# HX711_BrewSwitchSense_Preinfusion.net
KiCad netlist of a schematic drawn in EAGLE
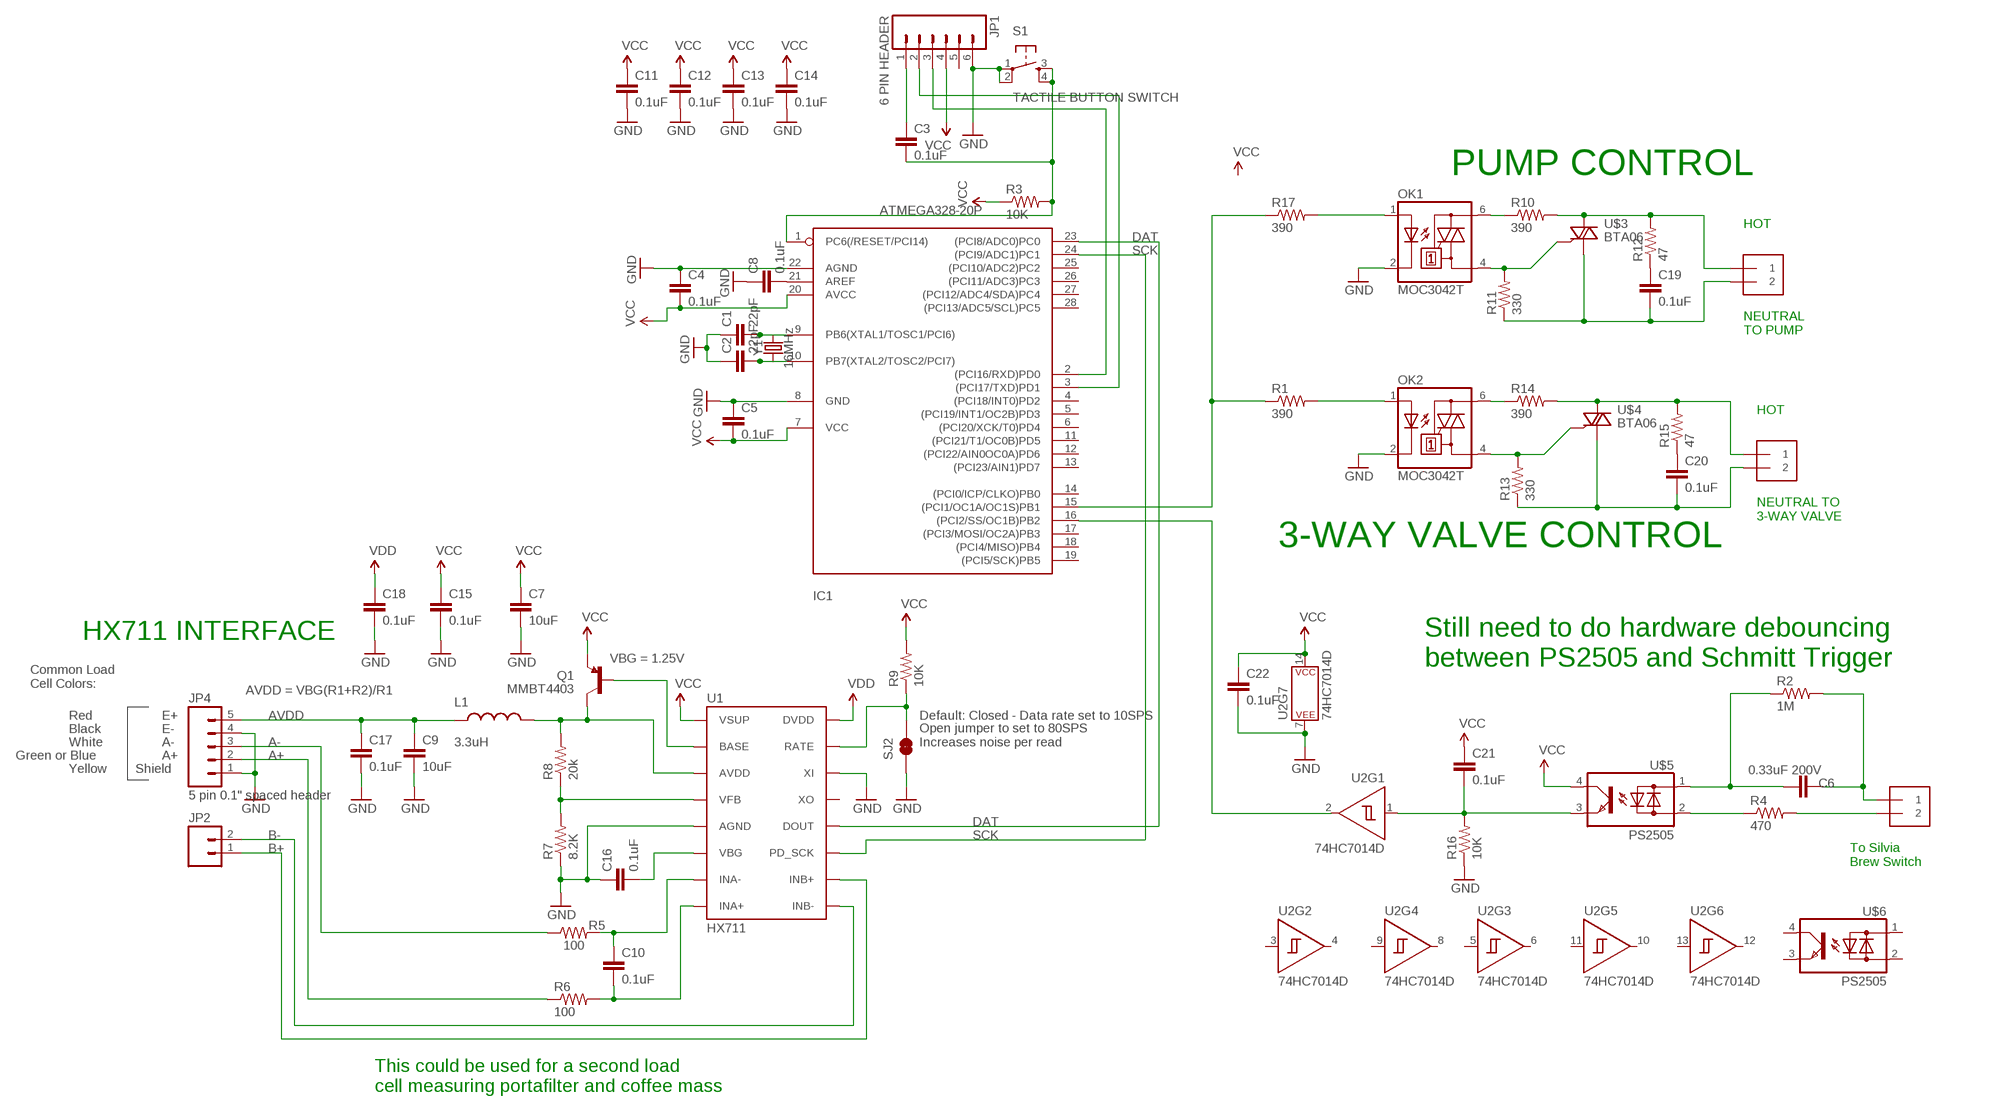
[diagram p0: schematic, sheet 1]

(export (version "E")
  (design (tool "Eeschema 10.0.6"))
  (components
    (comp (ref "C1")
      (value "22pF")
      (footprint "eagle-import:CAP-PTH-SMALL-KIT")
      (libsource (lib "eagle-import") (part "CAPKIT"))
    )
    (comp (ref "C2")
      (value "22pF")
      (footprint "eagle-import:CAP-PTH-SMALL-KIT")
      (libsource (lib "eagle-import") (part "CAPKIT"))
    )
    (comp (ref "C3")
      (value "0.1uF")
      (footprint "eagle-import:CAP-PTH-SMALLEZ")
      (libsource (lib "eagle-import") (part "CAPEZ"))
    )
    (comp (ref "C4")
      (value "0.1uF")
      (footprint "eagle-import:CAP-PTH-SMALLEZ")
      (libsource (lib "eagle-import") (part "CAPEZ"))
    )
    (comp (ref "C5")
      (value "0.1uF")
      (footprint "eagle-import:CAP-PTH-SMALLEZ")
      (libsource (lib "eagle-import") (part "CAPEZ"))
    )
    (comp (ref "C6")
      (value "0.33uF 200V")
      (footprint "eagle-import:C15B6")
      (libsource (lib "eagle-import") (part "C15/6"))
    )
    (comp (ref "C7")
      (value "10uF")
      (footprint "eagle-import:1210")
      (libsource (lib "eagle-import") (part "10UF50V20%(1210)"))
    )
    (comp (ref "C8")
      (value "0.1uF")
      (footprint "eagle-import:CAP-PTH-SMALLEZ")
      (libsource (lib "eagle-import") (part "CAPEZ"))
    )
    (comp (ref "C9")
      (value "10uF")
      (footprint "eagle-import:1210")
      (libsource (lib "eagle-import") (part "10UF50V20%(1210)"))
    )
    (comp (ref "C10")
      (value "0.1uF")
      (footprint "eagle-import:0603-CAP")
      (libsource (lib "eagle-import") (part "0.1UF-25V-5%(0603)"))
    )
    (comp (ref "C11")
      (value "0.1uF")
      (footprint "eagle-import:CAP-PTH-SMALLEZ")
      (libsource (lib "eagle-import") (part "CAPEZ"))
    )
    (comp (ref "C12")
      (value "0.1uF")
      (footprint "eagle-import:CAP-PTH-SMALLEZ")
      (libsource (lib "eagle-import") (part "CAPEZ"))
    )
    (comp (ref "C13")
      (value "0.1uF")
      (footprint "eagle-import:CAP-PTH-SMALLEZ")
      (libsource (lib "eagle-import") (part "CAPEZ"))
    )
    (comp (ref "C14")
      (value "0.1uF")
      (footprint "eagle-import:CAP-PTH-SMALLEZ")
      (libsource (lib "eagle-import") (part "CAPEZ"))
    )
    (comp (ref "C15")
      (value "0.1uF")
      (footprint "eagle-import:0603-CAP")
      (libsource (lib "eagle-import") (part "0.1UF-25V-5%(0603)"))
    )
    (comp (ref "C16")
      (value "0.1uF")
      (footprint "eagle-import:0603-CAP")
      (libsource (lib "eagle-import") (part "0.1UF-25V-5%(0603)"))
    )
    (comp (ref "C17")
      (value "0.1uF")
      (footprint "eagle-import:0603-CAP")
      (libsource (lib "eagle-import") (part "0.1UF-25V-5%(0603)"))
    )
    (comp (ref "C18")
      (value "0.1uF")
      (footprint "eagle-import:0603-CAP")
      (libsource (lib "eagle-import") (part "0.1UF-25V-5%(0603)"))
    )
    (comp (ref "C19")
      (value "0.1uF")
      (footprint "eagle-import:CAP-PTH-SMALLEZ")
      (libsource (lib "eagle-import") (part "CAPEZ"))
    )
    (comp (ref "C20")
      (value "0.1uF")
      (footprint "eagle-import:CAP-PTH-SMALLEZ")
      (libsource (lib "eagle-import") (part "CAPEZ"))
    )
    (comp (ref "C21")
      (value "0.1uF")
      (footprint "eagle-import:CAP-PTH-SMALLEZ")
      (libsource (lib "eagle-import") (part "CAPEZ"))
    )
    (comp (ref "C22")
      (value "0.1uF")
      (footprint "eagle-import:CAP-PTH-SMALLEZ")
      (libsource (lib "eagle-import") (part "CAPEZ"))
    )
    (comp (ref "IC1")
      (value "ATMEGA328-20P")
      (footprint "eagle-import:DIL28-3")
      (libsource (lib "eagle-import") (part "ATMEGA328P-20"))
    )
    (comp (ref "J2")
      (value "1X2-3.5MM")
      (footprint "eagle-import:1X2-3.5MM")
      (libsource (lib "eagle-import") (part "1X2-3.5MM"))
    )
    (comp (ref "J3")
      (value "1X2-3.5MM")
      (footprint "eagle-import:1X2-3.5MM")
      (libsource (lib "eagle-import") (part "1X2-3.5MM"))
    )
    (comp (ref "J4")
      (value "1X2-3.5MM")
      (footprint "eagle-import:1X2-3.5MM")
      (libsource (lib "eagle-import") (part "1X2-3.5MM"))
    )
    (comp (ref "JP1")
      (value "6 PIN HEADER")
      (footprint "eagle-import:1X06_LOCK_LONGPADS")
      (libsource (lib "eagle-import") (part "M06LOCK_LONGPADS"))
    )
    (comp (ref "JP2")
      (value "M02PTH")
      (footprint "eagle-import:1X02")
      (libsource (lib "eagle-import") (part "M02PTH"))
    )
    (comp (ref "JP4")
      (value "5 pin 0.1\" spaced header")
      (footprint "eagle-import:1X05")
      (libsource (lib "eagle-import") (part "M05PTH"))
    )
    (comp (ref "L1")
      (value "3.3uH")
      (footprint "eagle-import:0805")
      (libsource (lib "eagle-import") (part "INDUCTOR0805-IND"))
    )
    (comp (ref "OK1")
      (value "MOC3042T")
      (footprint "eagle-import:DIL06B")
      (libsource (lib "eagle-import") (part "MOC30T42"))
    )
    (comp (ref "OK2")
      (value "MOC3042T")
      (footprint "eagle-import:DIL06B")
      (libsource (lib "eagle-import") (part "MOC30T42"))
    )
    (comp (ref "Q1")
      (value "MMBT4403")
      (footprint "eagle-import:SOT23-3")
      (libsource (lib "eagle-import") (part "TRANSISTOR_PNPMMBT4403"))
    )
    (comp (ref "R1")
      (value "390")
      (footprint "eagle-import:AXIAL-0.5")
      (libsource (lib "eagle-import") (part "RESISTORPTH-1/2W"))
    )
    (comp (ref "R2")
      (value "1M")
      (footprint "eagle-import:1_6W-RES")
      (libsource (lib "eagle-import") (part "RESISTORPTH-1/6W"))
    )
    (comp (ref "R3")
      (value "10K")
      (footprint "eagle-import:AXIAL-0.5")
      (libsource (lib "eagle-import") (part "RESISTORPTH-1/2W"))
    )
    (comp (ref "R4")
      (value "470")
      (footprint "eagle-import:AXIAL-0.3-KIT")
      (libsource (lib "eagle-import") (part "RESISTORKIT"))
    )
    (comp (ref "R5")
      (value "100")
      (footprint "eagle-import:0603-RES")
      (libsource (lib "eagle-import") (part "100OHM-1/10W-1%(0603)"))
    )
    (comp (ref "R6")
      (value "100")
      (footprint "eagle-import:0603-RES")
      (libsource (lib "eagle-import") (part "100OHM-1/10W-1%(0603)"))
    )
    (comp (ref "R7")
      (value "8.2K")
      (footprint "eagle-import:0603-RES")
      (libsource (lib "eagle-import") (part "8.2KOHM-1/10W-5%(0603)"))
    )
    (comp (ref "R8")
      (value "20k")
      (footprint "eagle-import:0603-RES")
      (libsource (lib "eagle-import") (part "20KOHM1/10W1%(0603)"))
    )
    (comp (ref "R9")
      (value "10K")
      (footprint "eagle-import:0603-RES")
      (libsource (lib "eagle-import") (part "10KOHM-1/10W-1%(0603)0603"))
    )
    (comp (ref "R10")
      (value "390")
      (footprint "eagle-import:AXIAL-0.5")
      (libsource (lib "eagle-import") (part "RESISTORPTH-1/2W"))
    )
    (comp (ref "R11")
      (value "330")
      (footprint "eagle-import:AXIAL-0.5")
      (libsource (lib "eagle-import") (part "RESISTORPTH-1/2W"))
    )
    (comp (ref "R12")
      (value "47")
      (footprint "eagle-import:AXIAL-0.5")
      (libsource (lib "eagle-import") (part "RESISTORPTH-1/2W"))
    )
    (comp (ref "R13")
      (value "330")
      (footprint "eagle-import:AXIAL-0.5")
      (libsource (lib "eagle-import") (part "RESISTORPTH-1/2W"))
    )
    (comp (ref "R14")
      (value "390")
      (footprint "eagle-import:AXIAL-0.5")
      (libsource (lib "eagle-import") (part "RESISTORPTH-1/2W"))
    )
    (comp (ref "R15")
      (value "47")
      (footprint "eagle-import:AXIAL-0.5")
      (libsource (lib "eagle-import") (part "RESISTORPTH-1/2W"))
    )
    (comp (ref "R16")
      (value "10K")
      (footprint "eagle-import:AXIAL-0.5")
      (libsource (lib "eagle-import") (part "RESISTORPTH-1/2W"))
    )
    (comp (ref "R17")
      (value "390")
      (footprint "eagle-import:AXIAL-0.5")
      (libsource (lib "eagle-import") (part "RESISTORPTH-1/2W"))
    )
    (comp (ref "S1")
      (value "TACTILE BUTTON SWITCH")
      (footprint "eagle-import:TACTILE-PTH")
      (libsource (lib "eagle-import") (part "TAC_SWITCHPTH"))
    )
    (comp (ref "SJ2")
      (value "JUMPER-PAD-2-NC_BY_TRACE")
      (footprint "eagle-import:PAD-JUMPER-2-NC_BY_TRACE_YES_SILK")
      (libsource (lib "eagle-import") (part "JUMPER-PAD-2-NC_BY_TRACE"))
    )
    (comp (ref "U$3")
      (value "BTA06")
      (footprint "eagle-import:TO220V")
      (libsource (lib "eagle-import") (part "BTA06"))
    )
    (comp (ref "U$4")
      (value "BTA06")
      (footprint "eagle-import:TO220V")
      (libsource (lib "eagle-import") (part "BTA06"))
    )
    (comp (ref "U$5")
      (value "PS2505")
      (footprint "eagle-import:DIL04")
      (libsource (lib "eagle-import") (part "PS2505"))
    )
    (comp (ref "U$6")
      (value "PS2505")
      (footprint "eagle-import:DIL04")
      (libsource (lib "eagle-import") (part "PS2505"))
    )
    (comp (ref "U1")
      (value "HX711")
      (footprint "eagle-import:SO16")
      (libsource (lib "eagle-import") (part "HX711HX711"))
    )
    (comp (ref "U2")
      (value "74HC7014D")
      (footprint "eagle-import:SO14")
      (libsource (lib "eagle-import") (part "747014DHC"))
    )
    (comp (ref "Y1")
      (value "16MHz")
      (footprint "eagle-import:HC49US")
      (libsource (lib "eagle-import") (part "CRYSTAL-16MHZPTH-HC49US"))
    )
  )
  (nets
    (net (code "1") (name "/A+") (class "Default")
      (node (ref "JP4") (pin "2") (pinfunction "2_2") (pintype "passive"))
      (node (ref "R6") (pin "1") (pinfunction "1_1") (pintype "passive"))
    )
    (net (code "2") (name "/A-") (class "Default")
      (node (ref "JP4") (pin "3") (pinfunction "3_3") (pintype "passive"))
      (node (ref "R5") (pin "1") (pinfunction "1_1") (pintype "passive"))
    )
    (net (code "3") (name "/AVDD") (class "Default")
      (node (ref "C17") (pin "1") (pinfunction "1_1") (pintype "passive"))
      (node (ref "C9") (pin "1") (pinfunction "1_1") (pintype "passive"))
      (node (ref "JP4") (pin "5") (pinfunction "5_5") (pintype "passive"))
      (node (ref "L1") (pin "1") (pinfunction "1_1") (pintype "passive"))
    )
    (net (code "4") (name "/B+") (class "Default")
      (node (ref "JP2") (pin "1") (pinfunction "1_1") (pintype "passive"))
      (node (ref "U1") (pin "10") (pinfunction "INB+_10") (pintype "bidirectional"))
    )
    (net (code "5") (name "/B-") (class "Default")
      (node (ref "JP2") (pin "2") (pinfunction "2_2") (pintype "passive"))
      (node (ref "U1") (pin "9") (pinfunction "INB-_9") (pintype "bidirectional"))
    )
    (net (code "6") (name "/DAT") (class "Default")
      (node (ref "IC1") (pin "23") (pinfunction "(PCI8/ADC0)PC0_23") (pintype "bidirectional"))
      (node (ref "U1") (pin "12") (pinfunction "DOUT_12") (pintype "bidirectional"))
    )
    (net (code "7") (name "/SCK") (class "Default")
      (node (ref "IC1") (pin "24") (pinfunction "(PCI9/ADC1)PC1_24") (pintype "bidirectional"))
      (node (ref "U1") (pin "11") (pinfunction "PD_SCK_11") (pintype "bidirectional"))
    )
    (net (code "8") (name "GND") (class "Default")
      (node (ref "C1") (pin "1") (pinfunction "1_1") (pintype "passive"))
      (node (ref "C11") (pin "2") (pinfunction "2_2") (pintype "passive"))
      (node (ref "C12") (pin "2") (pinfunction "2_2") (pintype "passive"))
      (node (ref "C13") (pin "2") (pinfunction "2_2") (pintype "passive"))
      (node (ref "C14") (pin "2") (pinfunction "2_2") (pintype "passive"))
      (node (ref "C15") (pin "2") (pinfunction "2_2") (pintype "passive"))
      (node (ref "C16") (pin "1") (pinfunction "1_1") (pintype "passive"))
      (node (ref "C17") (pin "2") (pinfunction "2_2") (pintype "passive"))
      (node (ref "C18") (pin "2") (pinfunction "2_2") (pintype "passive"))
      (node (ref "C2") (pin "1") (pinfunction "1_1") (pintype "passive"))
      (node (ref "C22") (pin "2") (pinfunction "2_2") (pintype "passive"))
      (node (ref "C4") (pin "1") (pinfunction "1_1") (pintype "passive"))
      (node (ref "C5") (pin "1") (pinfunction "1_1") (pintype "passive"))
      (node (ref "C7") (pin "2") (pinfunction "2_2") (pintype "passive"))
      (node (ref "C8") (pin "1") (pinfunction "1_1") (pintype "passive"))
      (node (ref "C9") (pin "2") (pinfunction "2_2") (pintype "passive"))
      (node (ref "IC1") (pin "22") (pinfunction "AGND_22") (pintype "bidirectional"))
      (node (ref "IC1") (pin "8") (pinfunction "GND_8") (pintype "bidirectional"))
      (node (ref "JP1") (pin "6") (pinfunction "6_6") (pintype "passive"))
      (node (ref "JP4") (pin "1") (pinfunction "1_1") (pintype "passive"))
      (node (ref "JP4") (pin "4") (pinfunction "4_4") (pintype "passive"))
      (node (ref "OK1") (pin "2") (pinfunction "C_2") (pintype "passive"))
      (node (ref "OK2") (pin "2") (pinfunction "C_2") (pintype "passive"))
      (node (ref "R16") (pin "P$1") (pinfunction "1_P$1") (pintype "passive"))
      (node (ref "R7") (pin "1") (pinfunction "1_1") (pintype "passive"))
      (node (ref "S1") (pin "1") (pinfunction "1_1") (pintype "passive"))
      (node (ref "S1") (pin "2") (pinfunction "2_2") (pintype "passive"))
      (node (ref "SJ2") (pin "1") (pinfunction "1_1") (pintype "passive"))
      (node (ref "U1") (pin "14") (pinfunction "XI_14") (pintype "bidirectional"))
      (node (ref "U1") (pin "5") (pinfunction "AGND_5") (pintype "bidirectional"))
      (node (ref "U2") (pin "7") (pinfunction "P$V-_7") (pintype "bidirectional"))
    )
    (net (code "9") (name "Net-(C3-Pad1)") (class "Default")
      (node (ref "C3") (pin "1") (pinfunction "1_1") (pintype "passive"))
      (node (ref "JP1") (pin "1") (pinfunction "1_1") (pintype "passive"))
    )
    (net (code "10") (name "Net-(C6-Pad2)") (class "Default")
      (node (ref "C6") (pin "2") (pinfunction "2_2") (pintype "passive"))
      (node (ref "J2") (pin "1") (pinfunction "1_1") (pintype "passive"))
      (node (ref "R2") (pin "2") (pinfunction "2_2") (pintype "passive"))
    )
    (net (code "11") (name "Net-(IC1-(PCI1{slash}OC1A{slash}OC1S)PB1)") (class "Default")
      (node (ref "IC1") (pin "15") (pinfunction "(PCI1/OC1A/OC1S)PB1_15") (pintype "bidirectional"))
      (node (ref "R1") (pin "P$1") (pinfunction "1_P$1") (pintype "passive"))
      (node (ref "R17") (pin "P$1") (pinfunction "1_P$1") (pintype "passive"))
    )
    (net (code "12") (name "Net-(IC1-(PCI2{slash}SS{slash}OC1B)PB2)") (class "Default")
      (node (ref "IC1") (pin "16") (pinfunction "(PCI2/SS/OC1B)PB2_16") (pintype "bidirectional"))
      (node (ref "U2") (pin "2") (pinfunction "Y_2") (pintype "bidirectional"))
    )
    (net (code "13") (name "Net-(IC1-(PCI16{slash}RXD)PD0)") (class "Default")
      (node (ref "IC1") (pin "2") (pinfunction "(PCI16/RXD)PD0_2") (pintype "bidirectional"))
      (node (ref "JP1") (pin "3") (pinfunction "3_3") (pintype "passive"))
    )
    (net (code "14") (name "Net-(IC1-(PCI17{slash}TXD)PD1)") (class "Default")
      (node (ref "IC1") (pin "3") (pinfunction "(PCI17/TXD)PD1_3") (pintype "bidirectional"))
      (node (ref "JP1") (pin "2") (pinfunction "2_2") (pintype "passive"))
    )
    (net (code "15") (name "Net-(IC1-AREF)") (class "Default")
      (node (ref "C8") (pin "2") (pinfunction "2_2") (pintype "passive"))
      (node (ref "IC1") (pin "21") (pinfunction "AREF_21") (pintype "bidirectional"))
    )
    (net (code "16") (name "Net-(IC1-PB6(XTAL1{slash}TOSC1{slash}PCI6))") (class "Default")
      (node (ref "C1") (pin "2") (pinfunction "2_2") (pintype "passive"))
      (node (ref "IC1") (pin "9") (pinfunction "PB6(XTAL1/TOSC1/PCI6)_9") (pintype "bidirectional"))
      (node (ref "Y1") (pin "2") (pinfunction "2_2") (pintype "passive"))
    )
    (net (code "17") (name "Net-(IC1-PB7(XTAL2{slash}TOSC2{slash}PCI7))") (class "Default")
      (node (ref "C2") (pin "2") (pinfunction "2_2") (pintype "passive"))
      (node (ref "IC1") (pin "10") (pinfunction "PB7(XTAL2/TOSC2/PCI7)_10") (pintype "bidirectional"))
      (node (ref "Y1") (pin "1") (pinfunction "1_1") (pintype "passive"))
    )
    (net (code "18") (name "Net-(IC1-PC6({slash}RESET{slash}PCI14))") (class "Default")
      (node (ref "C3") (pin "2") (pinfunction "2_2") (pintype "passive"))
      (node (ref "IC1") (pin "1") (pinfunction "PC6(/RESET/PCI14)_1") (pintype "bidirectional"))
      (node (ref "R3") (pin "P$2") (pinfunction "2_P$2") (pintype "passive"))
      (node (ref "S1") (pin "3") (pinfunction "3_3") (pintype "passive"))
      (node (ref "S1") (pin "4") (pinfunction "4_4") (pintype "passive"))
    )
    (net (code "19") (name "Net-(OK1-A)") (class "Default")
      (node (ref "OK1") (pin "1") (pinfunction "A_1") (pintype "passive"))
      (node (ref "R17") (pin "P$2") (pinfunction "2_P$2") (pintype "passive"))
    )
    (net (code "20") (name "Net-(OK1-A1)") (class "Default")
      (node (ref "OK1") (pin "4") (pinfunction "A1_4") (pintype "passive"))
      (node (ref "R11") (pin "P$2") (pinfunction "2_P$2") (pintype "passive"))
      (node (ref "U$3") (pin "3") (pinfunction "G_3") (pintype "passive"))
    )
    (net (code "21") (name "Net-(OK1-A2)") (class "Default")
      (node (ref "OK1") (pin "6") (pinfunction "A2_6") (pintype "passive"))
      (node (ref "R10") (pin "P$1") (pinfunction "1_P$1") (pintype "passive"))
    )
    (net (code "22") (name "Net-(OK2-A)") (class "Default")
      (node (ref "OK2") (pin "1") (pinfunction "A_1") (pintype "passive"))
      (node (ref "R1") (pin "P$2") (pinfunction "2_P$2") (pintype "passive"))
    )
    (net (code "23") (name "Net-(OK2-A1)") (class "Default")
      (node (ref "OK2") (pin "4") (pinfunction "A1_4") (pintype "passive"))
      (node (ref "R13") (pin "P$2") (pinfunction "2_P$2") (pintype "passive"))
      (node (ref "U$4") (pin "3") (pinfunction "G_3") (pintype "passive"))
    )
    (net (code "24") (name "Net-(OK2-A2)") (class "Default")
      (node (ref "OK2") (pin "6") (pinfunction "A2_6") (pintype "passive"))
      (node (ref "R14") (pin "P$1") (pinfunction "1_P$1") (pintype "passive"))
    )
    (net (code "25") (name "Net-(Q1-B)") (class "Default")
      (node (ref "Q1") (pin "1") (pinfunction "B_1") (pintype "passive"))
      (node (ref "U1") (pin "2") (pinfunction "BASE_2") (pintype "bidirectional"))
    )
    (net (code "26") (name "Net-(Q1-C)") (class "Default")
      (node (ref "L1") (pin "2") (pinfunction "2_2") (pintype "passive"))
      (node (ref "Q1") (pin "3") (pinfunction "C_3") (pintype "passive"))
      (node (ref "R8") (pin "2") (pinfunction "2_2") (pintype "passive"))
      (node (ref "U1") (pin "3") (pinfunction "AVDD_3") (pintype "bidirectional"))
    )
    (net (code "27") (name "Net-(R4-1)") (class "Default")
      (node (ref "R4") (pin "P$1") (pinfunction "1_P$1") (pintype "passive"))
      (node (ref "U$5") (pin "2") (pinfunction "AC2_2") (pintype "passive"))
    )
    (net (code "28") (name "Net-(R4-2)") (class "Default")
      (node (ref "J2") (pin "2") (pinfunction "2_2") (pintype "passive"))
      (node (ref "R4") (pin "P$2") (pinfunction "2_P$2") (pintype "passive"))
    )
    (net (code "29") (name "Net-(R10-2)") (class "Default")
      (node (ref "J3") (pin "1") (pinfunction "1_1") (pintype "passive"))
      (node (ref "R10") (pin "P$2") (pinfunction "2_P$2") (pintype "passive"))
      (node (ref "R12") (pin "P$2") (pinfunction "2_P$2") (pintype "passive"))
      (node (ref "U$3") (pin "2") (pinfunction "A2_2") (pintype "passive"))
    )
    (net (code "30") (name "Net-(R11-1)") (class "Default")
      (node (ref "C19") (pin "2") (pinfunction "2_2") (pintype "passive"))
      (node (ref "J3") (pin "2") (pinfunction "2_2") (pintype "passive"))
      (node (ref "R11") (pin "P$1") (pinfunction "1_P$1") (pintype "passive"))
      (node (ref "U$3") (pin "1") (pinfunction "A1_1") (pintype "passive"))
    )
    (net (code "31") (name "Net-(R12-1)") (class "Default")
      (node (ref "C19") (pin "1") (pinfunction "1_1") (pintype "passive"))
      (node (ref "R12") (pin "P$1") (pinfunction "1_P$1") (pintype "passive"))
    )
    (net (code "32") (name "Net-(R13-1)") (class "Default")
      (node (ref "C20") (pin "2") (pinfunction "2_2") (pintype "passive"))
      (node (ref "J4") (pin "2") (pinfunction "2_2") (pintype "passive"))
      (node (ref "R13") (pin "P$1") (pinfunction "1_P$1") (pintype "passive"))
      (node (ref "U$4") (pin "1") (pinfunction "A1_1") (pintype "passive"))
    )
    (net (code "33") (name "Net-(R14-2)") (class "Default")
      (node (ref "J4") (pin "1") (pinfunction "1_1") (pintype "passive"))
      (node (ref "R14") (pin "P$2") (pinfunction "2_P$2") (pintype "passive"))
      (node (ref "R15") (pin "P$2") (pinfunction "2_P$2") (pintype "passive"))
      (node (ref "U$4") (pin "2") (pinfunction "A2_2") (pintype "passive"))
    )
    (net (code "34") (name "Net-(R15-1)") (class "Default")
      (node (ref "C20") (pin "1") (pinfunction "1_1") (pintype "passive"))
      (node (ref "R15") (pin "P$1") (pinfunction "1_P$1") (pintype "passive"))
    )
    (net (code "35") (name "Net-(R16-2)") (class "Default")
      (node (ref "C21") (pin "2") (pinfunction "2_2") (pintype "passive"))
      (node (ref "R16") (pin "P$2") (pinfunction "2_P$2") (pintype "passive"))
      (node (ref "U$5") (pin "3") (pinfunction "E_3") (pintype "passive"))
      (node (ref "U2") (pin "1") (pinfunction "A_1") (pintype "bidirectional"))
    )
    (net (code "36") (name "Net-(U$5-AC1)") (class "Default")
      (node (ref "C6") (pin "1") (pinfunction "1_1") (pintype "passive"))
      (node (ref "R2") (pin "1") (pinfunction "1_1") (pintype "passive"))
      (node (ref "U$5") (pin "1") (pinfunction "AC1_1") (pintype "passive"))
    )
    (net (code "37") (name "Net-(U1-INA+)") (class "Default")
      (node (ref "C10") (pin "2") (pinfunction "2_2") (pintype "passive"))
      (node (ref "R6") (pin "2") (pinfunction "2_2") (pintype "passive"))
      (node (ref "U1") (pin "8") (pinfunction "INA+_8") (pintype "bidirectional"))
    )
    (net (code "38") (name "Net-(U1-INA-)") (class "Default")
      (node (ref "C10") (pin "1") (pinfunction "1_1") (pintype "passive"))
      (node (ref "R5") (pin "2") (pinfunction "2_2") (pintype "passive"))
      (node (ref "U1") (pin "7") (pinfunction "INA-_7") (pintype "bidirectional"))
    )
    (net (code "39") (name "Net-(U1-RATE)") (class "Default")
      (node (ref "R9") (pin "1") (pinfunction "1_1") (pintype "passive"))
      (node (ref "SJ2") (pin "2") (pinfunction "2_2") (pintype "passive"))
      (node (ref "U1") (pin "15") (pinfunction "RATE_15") (pintype "bidirectional"))
    )
    (net (code "40") (name "Net-(U1-VBG)") (class "Default")
      (node (ref "C16") (pin "2") (pinfunction "2_2") (pintype "passive"))
      (node (ref "U1") (pin "6") (pinfunction "VBG_6") (pintype "bidirectional"))
    )
    (net (code "41") (name "Net-(U1-VFB)") (class "Default")
      (node (ref "R7") (pin "2") (pinfunction "2_2") (pintype "passive"))
      (node (ref "R8") (pin "1") (pinfunction "1_1") (pintype "passive"))
      (node (ref "U1") (pin "4") (pinfunction "VFB_4") (pintype "bidirectional"))
    )
    (net (code "42") (name "VCC") (class "Default")
      (node (ref "C11") (pin "1") (pinfunction "1_1") (pintype "passive"))
      (node (ref "C12") (pin "1") (pinfunction "1_1") (pintype "passive"))
      (node (ref "C13") (pin "1") (pinfunction "1_1") (pintype "passive"))
      (node (ref "C14") (pin "1") (pinfunction "1_1") (pintype "passive"))
      (node (ref "C15") (pin "1") (pinfunction "1_1") (pintype "passive"))
      (node (ref "C21") (pin "1") (pinfunction "1_1") (pintype "passive"))
      (node (ref "C22") (pin "1") (pinfunction "1_1") (pintype "passive"))
      (node (ref "C4") (pin "2") (pinfunction "2_2") (pintype "passive"))
      (node (ref "C5") (pin "2") (pinfunction "2_2") (pintype "passive"))
      (node (ref "C7") (pin "1") (pinfunction "1_1") (pintype "passive"))
      (node (ref "IC1") (pin "20") (pinfunction "AVCC_20") (pintype "bidirectional"))
      (node (ref "IC1") (pin "7") (pinfunction "VCC_7") (pintype "bidirectional"))
      (node (ref "JP1") (pin "4") (pinfunction "4_4") (pintype "passive"))
      (node (ref "Q1") (pin "2") (pinfunction "E_2") (pintype "passive"))
      (node (ref "R3") (pin "P$1") (pinfunction "1_P$1") (pintype "passive"))
      (node (ref "R9") (pin "2") (pinfunction "2_2") (pintype "passive"))
      (node (ref "U$5") (pin "4") (pinfunction "C_4") (pintype "passive"))
      (node (ref "U1") (pin "1") (pinfunction "VSUP_1") (pintype "bidirectional"))
      (node (ref "U2") (pin "14") (pinfunction "P$V+_14") (pintype "bidirectional"))
    )
    (net (code "43") (name "VDD") (class "Default")
      (node (ref "C18") (pin "1") (pinfunction "1_1") (pintype "passive"))
      (node (ref "U1") (pin "16") (pinfunction "DVDD_16") (pintype "bidirectional"))
    )
    (net (code "44") (name "unconnected-(IC1-(PCI0{slash}ICP{slash}CLKO)PB0-Pad14)") (class "Default")
      (node (ref "IC1") (pin "14") (pinfunction "(PCI0/ICP/CLKO)PB0_14") (pintype "bidirectional"))
    )
    (net (code "45") (name "unconnected-(IC1-(PCI3{slash}MOSI{slash}OC2A)PB3-Pad17)") (class "Default")
      (node (ref "IC1") (pin "17") (pinfunction "(PCI3/MOSI/OC2A)PB3_17") (pintype "bidirectional"))
    )
    (net (code "46") (name "unconnected-(IC1-(PCI4{slash}MISO)PB4-Pad18)") (class "Default")
      (node (ref "IC1") (pin "18") (pinfunction "(PCI4/MISO)PB4_18") (pintype "bidirectional"))
    )
    (net (code "47") (name "unconnected-(IC1-(PCI5{slash}SCK)PB5-Pad19)") (class "Default")
      (node (ref "IC1") (pin "19") (pinfunction "(PCI5/SCK)PB5_19") (pintype "bidirectional"))
    )
    (net (code "48") (name "unconnected-(IC1-(PCI10{slash}ADC2)PC2-Pad25)") (class "Default")
      (node (ref "IC1") (pin "25") (pinfunction "(PCI10/ADC2)PC2_25") (pintype "bidirectional"))
    )
    (net (code "49") (name "unconnected-(IC1-(PCI11{slash}ADC3)PC3-Pad26)") (class "Default")
      (node (ref "IC1") (pin "26") (pinfunction "(PCI11/ADC3)PC3_26") (pintype "bidirectional"))
    )
    (net (code "50") (name "unconnected-(IC1-(PCI12{slash}ADC4{slash}SDA)PC4-Pad27)") (class "Default")
      (node (ref "IC1") (pin "27") (pinfunction "(PCI12/ADC4/SDA)PC4_27") (pintype "bidirectional"))
    )
    (net (code "51") (name "unconnected-(IC1-(PCI13{slash}ADC5{slash}SCL)PC5-Pad28)") (class "Default")
      (node (ref "IC1") (pin "28") (pinfunction "(PCI13/ADC5/SCL)PC5_28") (pintype "bidirectional"))
    )
    (net (code "52") (name "unconnected-(IC1-(PCI18{slash}INT0)PD2-Pad4)") (class "Default")
      (node (ref "IC1") (pin "4") (pinfunction "(PCI18/INT0)PD2_4") (pintype "bidirectional"))
    )
    (net (code "53") (name "unconnected-(IC1-(PCI19{slash}INT1{slash}OC2B)PD3-Pad5)") (class "Default")
      (node (ref "IC1") (pin "5") (pinfunction "(PCI19/INT1/OC2B)PD3_5") (pintype "bidirectional"))
    )
    (net (code "54") (name "unconnected-(IC1-(PCI20{slash}XCK{slash}T0)PD4-Pad6)") (class "Default")
      (node (ref "IC1") (pin "6") (pinfunction "(PCI20/XCK/T0)PD4_6") (pintype "bidirectional"))
    )
    (net (code "55") (name "unconnected-(IC1-(PCI21{slash}T1{slash}OC0B)PD5-Pad11)") (class "Default")
      (node (ref "IC1") (pin "11") (pinfunction "(PCI21/T1/OC0B)PD5_11") (pintype "bidirectional"))
    )
    (net (code "56") (name "unconnected-(IC1-(PCI22{slash}AIN0OC0A)PD6-Pad12)") (class "Default")
      (node (ref "IC1") (pin "12") (pinfunction "(PCI22/AIN0OC0A)PD6_12") (pintype "bidirectional"))
    )
    (net (code "57") (name "unconnected-(IC1-(PCI23{slash}AIN1)PD7-Pad13)") (class "Default")
      (node (ref "IC1") (pin "13") (pinfunction "(PCI23/AIN1)PD7_13") (pintype "bidirectional"))
    )
    (net (code "58") (name "unconnected-(JP1-Pad5)") (class "Default")
      (node (ref "JP1") (pin "5") (pinfunction "5_5") (pintype "passive"))
    )
    (net (code "59") (name "unconnected-(U$6-AC1-Pad1)") (class "Default")
      (node (ref "U$6") (pin "1") (pinfunction "AC1_1") (pintype "passive"))
    )
    (net (code "60") (name "unconnected-(U$6-AC2-Pad2)") (class "Default")
      (node (ref "U$6") (pin "2") (pinfunction "AC2_2") (pintype "passive"))
    )
    (net (code "61") (name "unconnected-(U$6-C-Pad4)") (class "Default")
      (node (ref "U$6") (pin "4") (pinfunction "C_4") (pintype "passive"))
    )
    (net (code "62") (name "unconnected-(U$6-E-Pad3)") (class "Default")
      (node (ref "U$6") (pin "3") (pinfunction "E_3") (pintype "passive"))
    )
    (net (code "63") (name "unconnected-(U1-XO-Pad13)") (class "Default")
      (node (ref "U1") (pin "13") (pinfunction "XO_13") (pintype "bidirectional"))
    )
    (net (code "64") (name "unconnected-(U2B-A-Pad3)") (class "Default")
      (node (ref "U2") (pin "3") (pinfunction "A_3") (pintype "bidirectional"))
    )
    (net (code "65") (name "unconnected-(U2B-Y-Pad4)") (class "Default")
      (node (ref "U2") (pin "4") (pinfunction "Y_4") (pintype "bidirectional"))
    )
    (net (code "66") (name "unconnected-(U2C-A-Pad5)") (class "Default")
      (node (ref "U2") (pin "5") (pinfunction "A_5") (pintype "bidirectional"))
    )
    (net (code "67") (name "unconnected-(U2C-Y-Pad6)") (class "Default")
      (node (ref "U2") (pin "6") (pinfunction "Y_6") (pintype "bidirectional"))
    )
    (net (code "68") (name "unconnected-(U2D-A-Pad9)") (class "Default")
      (node (ref "U2") (pin "9") (pinfunction "A_9") (pintype "bidirectional"))
    )
    (net (code "69") (name "unconnected-(U2D-Y-Pad8)") (class "Default")
      (node (ref "U2") (pin "8") (pinfunction "Y_8") (pintype "bidirectional"))
    )
    (net (code "70") (name "unconnected-(U2E-A-Pad11)") (class "Default")
      (node (ref "U2") (pin "11") (pinfunction "A_11") (pintype "bidirectional"))
    )
    (net (code "71") (name "unconnected-(U2E-Y-Pad10)") (class "Default")
      (node (ref "U2") (pin "10") (pinfunction "Y_10") (pintype "bidirectional"))
    )
    (net (code "72") (name "unconnected-(U2F-A-Pad13)") (class "Default")
      (node (ref "U2") (pin "13") (pinfunction "A_13") (pintype "bidirectional"))
    )
    (net (code "73") (name "unconnected-(U2F-Y-Pad12)") (class "Default")
      (node (ref "U2") (pin "12") (pinfunction "Y_12") (pintype "bidirectional"))
    )
  )
)
